# Main_Power.net
KiCad netlist of a schematic drawn in Altium Designer
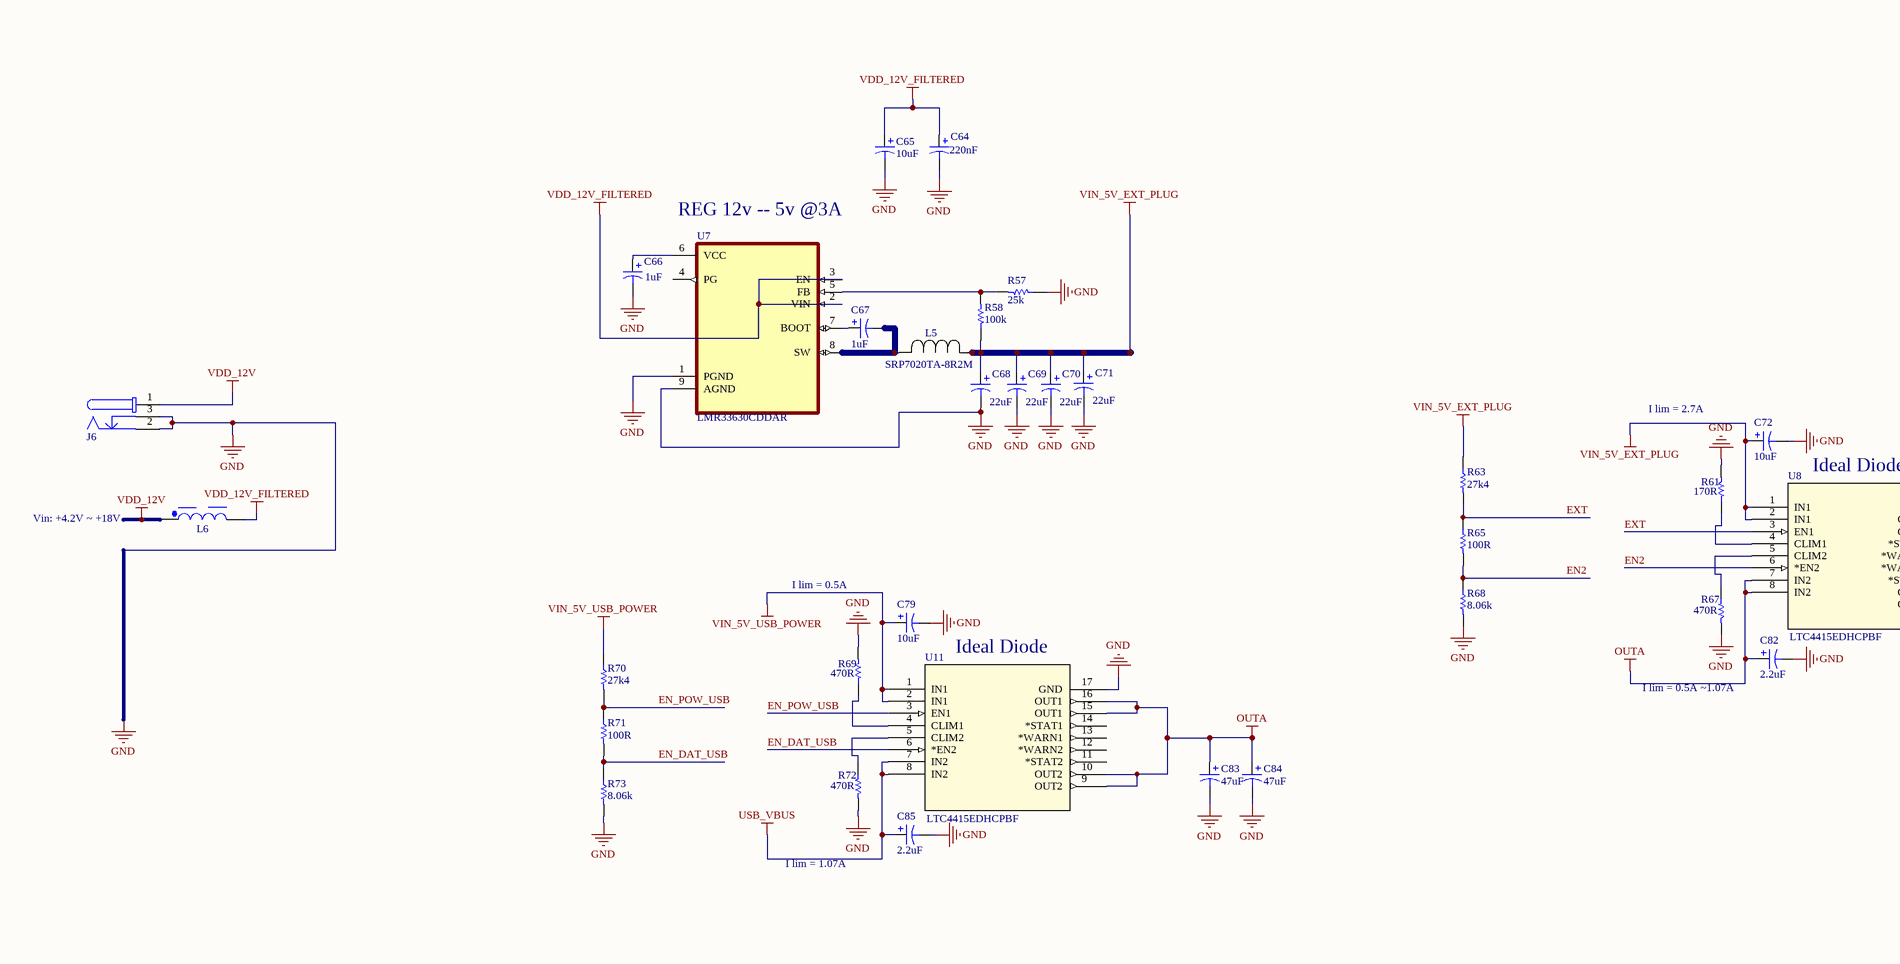
[diagram p0: Main_Power.SchDoc, top left]
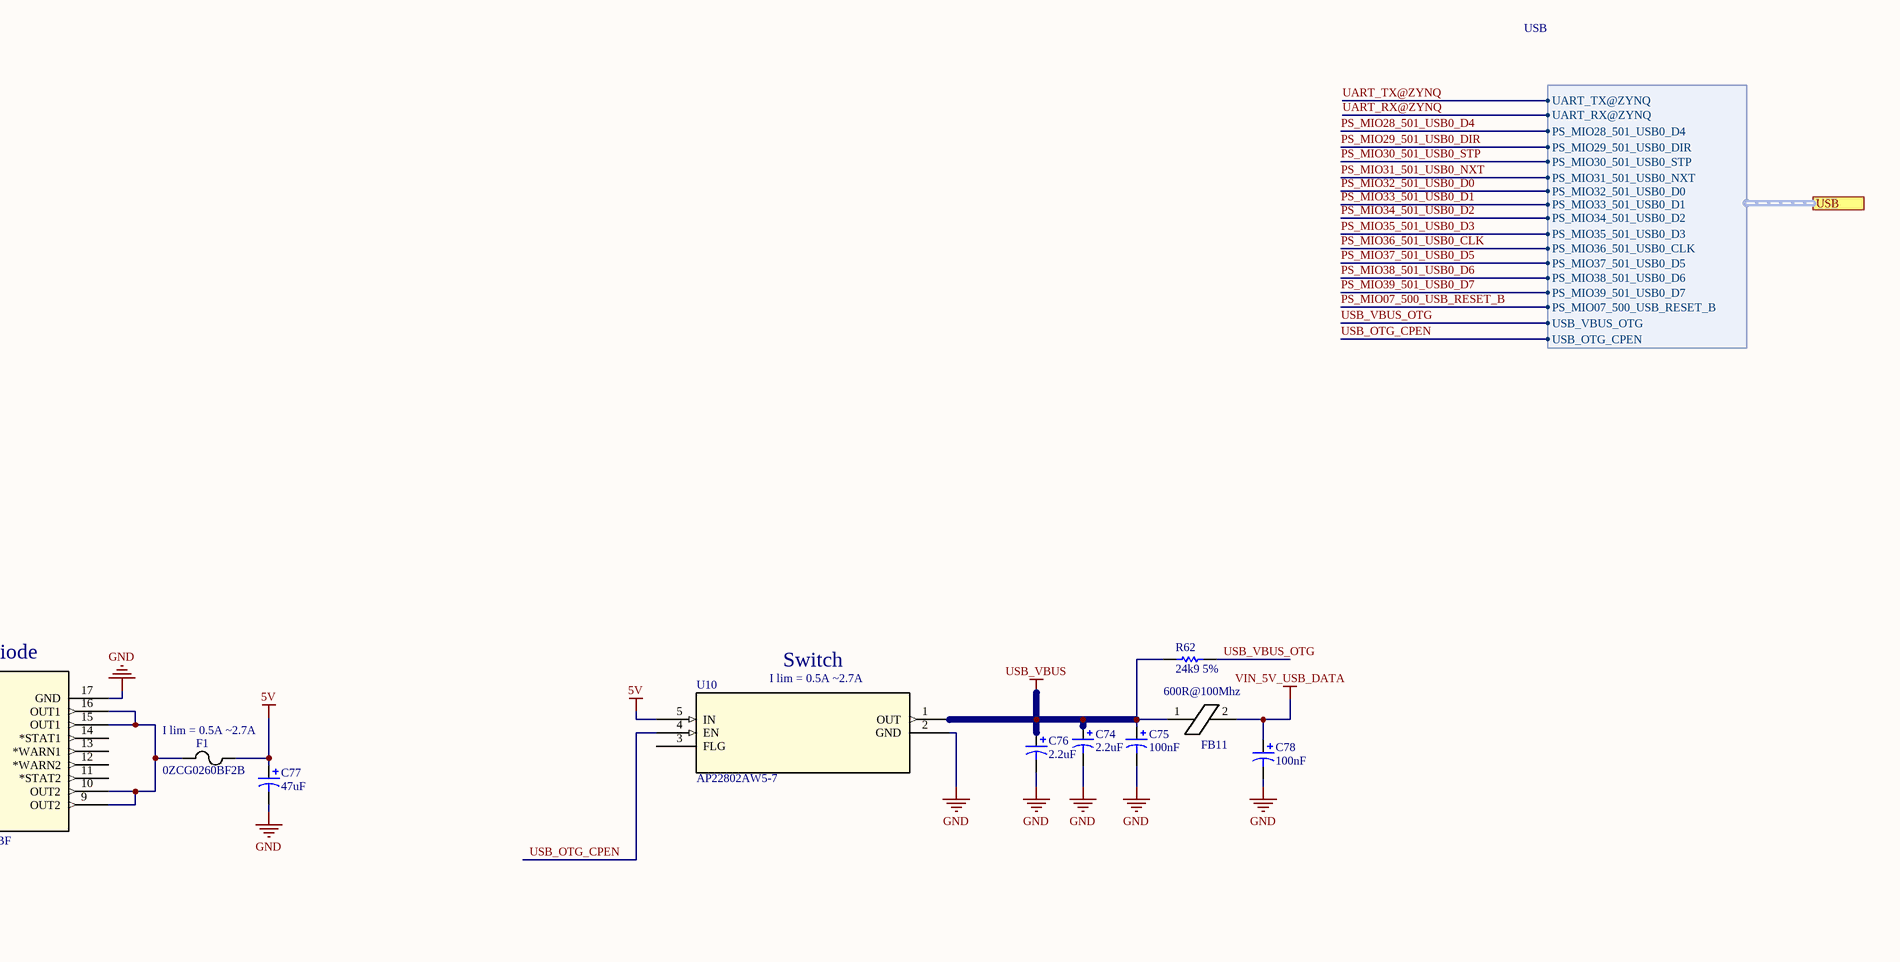
[diagram p1: Main_Power.SchDoc, top right]
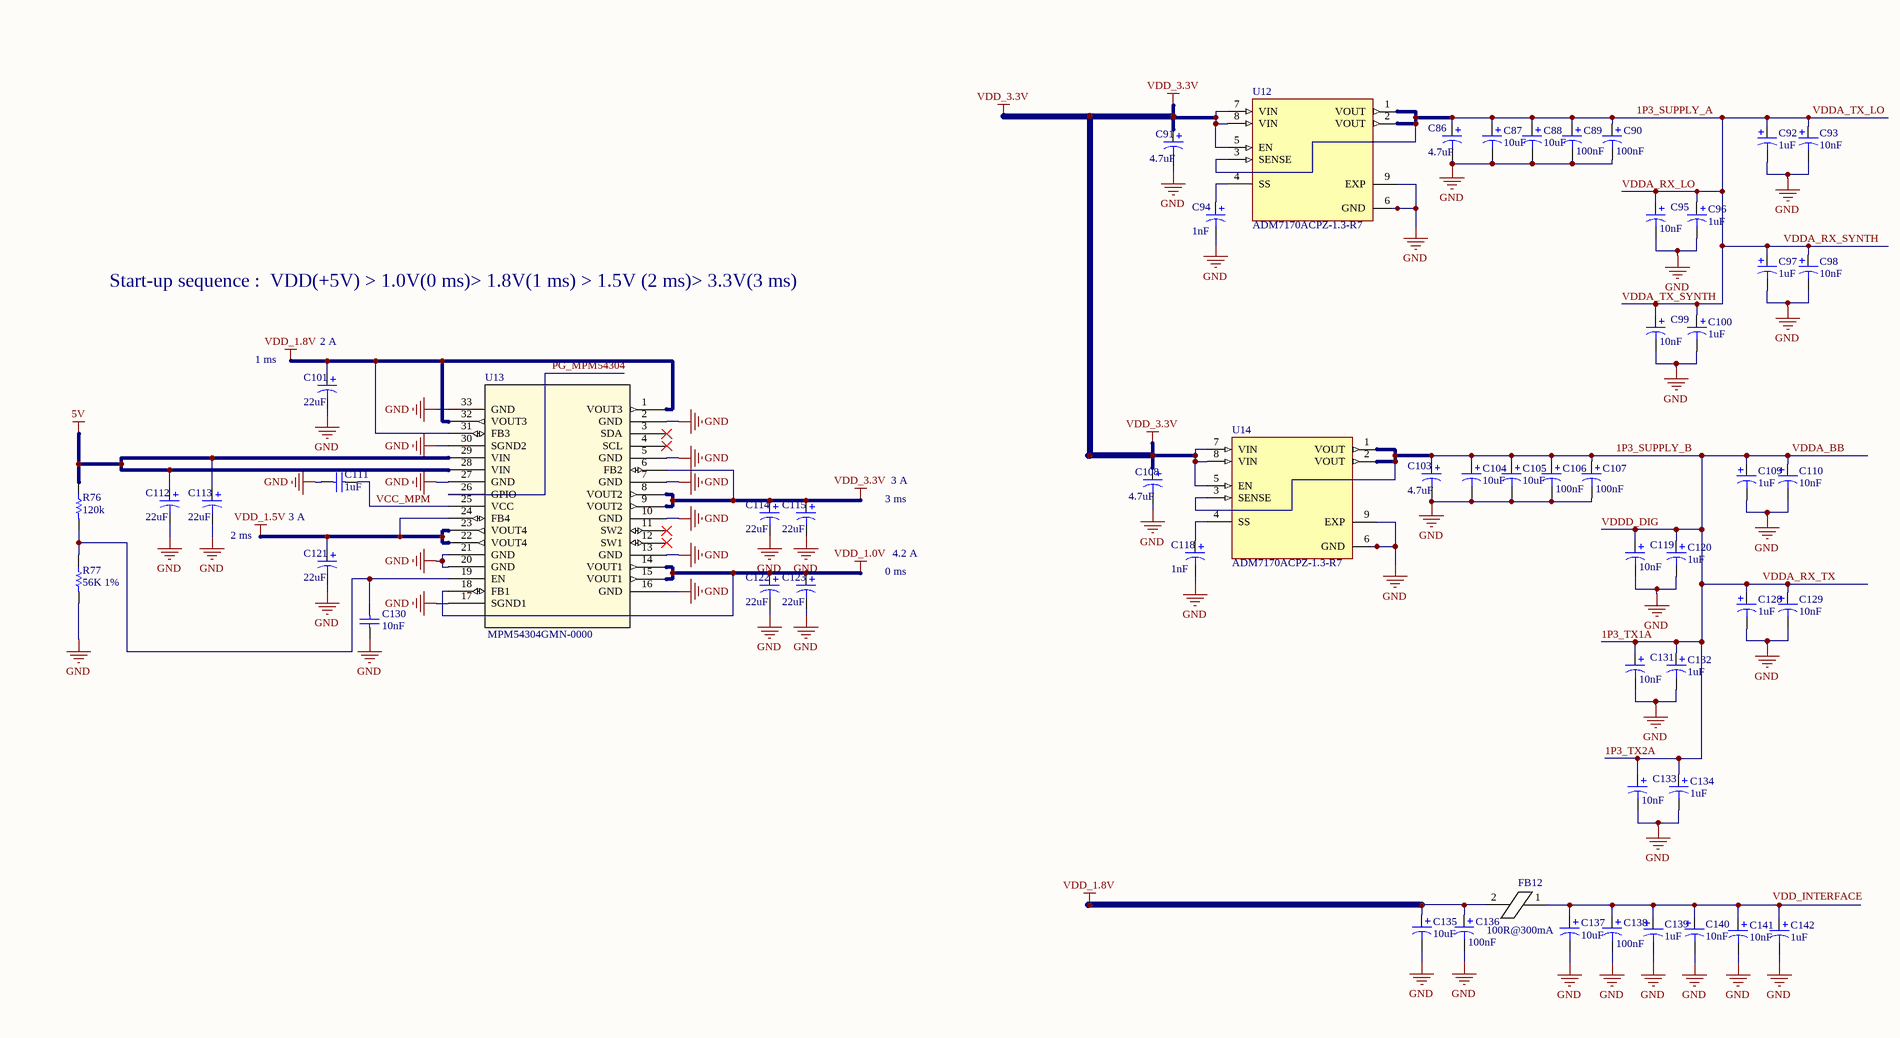
[diagram p2: Main_Power.SchDoc, bottom left]
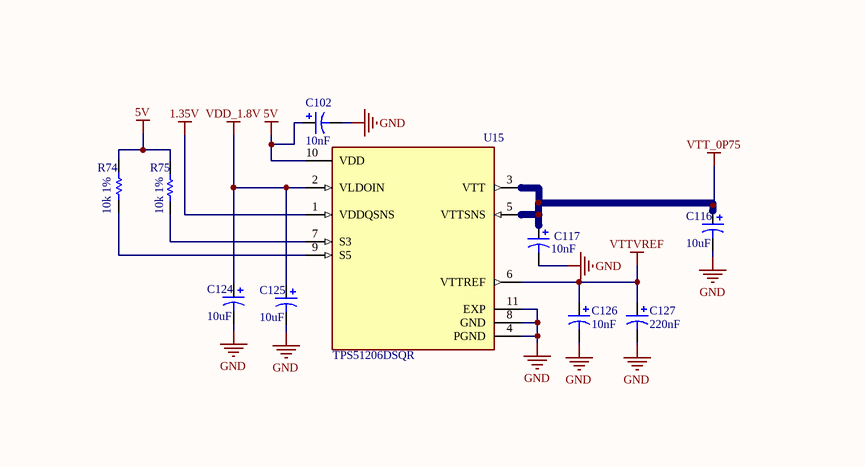
[diagram p3: Main_Power.SchDoc, bottom right]

(export (version "E")
  (design (tool "Eeschema 10.0.6"))
  (components
    (comp (ref "C64")
      (value "220nF")
      (footprint "C0805")
      (description "Polarized Capacitor (Surface Mount)")
      (fields (field (name "Comment") "Pol3") (field (name "PUBLISHER") "Altium Limited"))
      (libsource (lib "Miscellaneous Devices") (part "Cap Pol3"))
    )
    (comp (ref "C65")
      (value "10uF")
      (footprint "C0805")
      (description "Polarized Capacitor (Surface Mount)")
      (fields (field (name "Comment") "Cap Pol3") (field (name "PUBLISHER") "Altium Limited"))
      (libsource (lib "Miscellaneous Devices") (part "Cap Pol3"))
    )
    (comp (ref "C66")
      (value "1uF")
      (footprint "C0805")
      (description "Polarized Capacitor (Surface Mount)")
      (fields (field (name "Comment") "Pol3") (field (name "PUBLISHER") "Altium Limited"))
      (libsource (lib "Miscellaneous Devices") (part "Cap Pol3"))
    )
    (comp (ref "C67")
      (value "1uF")
      (footprint "C0805")
      (description "Polarized Capacitor (Surface Mount)")
      (fields (field (name "Comment") "Pol3") (field (name "PUBLISHER") "Altium Limited"))
      (libsource (lib "Miscellaneous Devices") (part "Cap Pol3"))
    )
    (comp (ref "C68")
      (value "22uF")
      (footprint "C0805")
      (description "Polarized Capacitor (Surface Mount)")
      (fields (field (name "Comment") "Pol3") (field (name "PUBLISHER") "Altium Limited"))
      (libsource (lib "Miscellaneous Devices") (part "Cap Pol3"))
    )
    (comp (ref "C69")
      (value "22uF")
      (footprint "C0805")
      (description "Polarized Capacitor (Surface Mount)")
      (fields (field (name "Comment") "Pol3") (field (name "PUBLISHER") "Altium Limited"))
      (libsource (lib "Miscellaneous Devices") (part "Cap Pol3"))
    )
    (comp (ref "C70")
      (value "22uF")
      (footprint "C0805")
      (description "Polarized Capacitor (Surface Mount)")
      (fields (field (name "Comment") "Pol3") (field (name "PUBLISHER") "Altium Limited"))
      (libsource (lib "Miscellaneous Devices") (part "Cap Pol3"))
    )
    (comp (ref "C71")
      (value "22uF")
      (footprint "C0805")
      (description "Polarized Capacitor (Surface Mount)")
      (fields (field (name "Comment") "Pol3") (field (name "PUBLISHER") "Altium Limited"))
      (libsource (lib "Miscellaneous Devices") (part "Cap Pol3"))
    )
    (comp (ref "C72")
      (value "10uF")
      (footprint "C0805")
      (description "Polarized Capacitor (Surface Mount)")
      (fields (field (name "Comment") "Cap Pol3") (field (name "PUBLISHER") "Altium Limited"))
      (libsource (lib "Miscellaneous Devices") (part "Cap Pol3"))
    )
    (comp (ref "C74")
      (value "2.2uF")
      (footprint "C0805")
      (description "Polarized Capacitor (Surface Mount)")
      (fields (field (name "Comment") "Cap Pol3") (field (name "PUBLISHER") "Altium Limited"))
      (libsource (lib "Miscellaneous Devices") (part "Cap Pol3"))
    )
    (comp (ref "C75")
      (value "100nF")
      (footprint "C0805")
      (description "Polarized Capacitor (Surface Mount)")
      (fields (field (name "Comment") "Cap Pol3") (field (name "PUBLISHER") "Altium Limited"))
      (libsource (lib "Miscellaneous Devices") (part "Cap Pol3"))
    )
    (comp (ref "C76")
      (value "2.2uF")
      (footprint "C0805")
      (description "Polarized Capacitor (Surface Mount)")
      (fields (field (name "Comment") "Cap Pol3") (field (name "PUBLISHER") "Altium Limited"))
      (libsource (lib "Miscellaneous Devices") (part "Cap Pol3"))
    )
    (comp (ref "C77")
      (value "47uF")
      (footprint "C0805")
      (description "Polarized Capacitor (Surface Mount)")
      (fields (field (name "Comment") "Cap Pol3") (field (name "PUBLISHER") "Altium Limited"))
      (libsource (lib "Miscellaneous Devices") (part "Cap Pol3"))
    )
    (comp (ref "C78")
      (value "100nF")
      (footprint "C0805")
      (description "Polarized Capacitor (Surface Mount)")
      (fields (field (name "Comment") "Cap Pol3") (field (name "PUBLISHER") "Altium Limited"))
      (libsource (lib "Miscellaneous Devices") (part "Cap Pol3"))
    )
    (comp (ref "C79")
      (value "10uF")
      (footprint "C0805")
      (description "Polarized Capacitor (Surface Mount)")
      (fields (field (name "Comment") "Cap Pol3") (field (name "PUBLISHER") "Altium Limited"))
      (libsource (lib "Miscellaneous Devices") (part "Cap Pol3"))
    )
    (comp (ref "C82")
      (value "2.2uF")
      (footprint "C0805")
      (description "Polarized Capacitor (Surface Mount)")
      (fields (field (name "Comment") "Cap Pol3") (field (name "PUBLISHER") "Altium Limited"))
      (libsource (lib "Miscellaneous Devices") (part "Cap Pol3"))
    )
    (comp (ref "C83")
      (value "47uF")
      (footprint "C0805")
      (description "Polarized Capacitor (Surface Mount)")
      (fields (field (name "Comment") "Cap Pol3") (field (name "PUBLISHER") "Altium Limited"))
      (libsource (lib "Miscellaneous Devices") (part "Cap Pol3"))
    )
    (comp (ref "C84")
      (value "47uF")
      (footprint "C0805")
      (description "Polarized Capacitor (Surface Mount)")
      (fields (field (name "Comment") "Cap Pol3") (field (name "PUBLISHER") "Altium Limited"))
      (libsource (lib "Miscellaneous Devices") (part "Cap Pol3"))
    )
    (comp (ref "C85")
      (value "2.2uF")
      (footprint "C0805")
      (description "Polarized Capacitor (Surface Mount)")
      (fields (field (name "Comment") "Cap Pol3") (field (name "PUBLISHER") "Altium Limited"))
      (libsource (lib "Miscellaneous Devices") (part "Cap Pol3"))
    )
    (comp (ref "C86")
      (value "4.7uF")
      (footprint "C0805")
      (description "Polarized Capacitor (Surface Mount)")
      (fields (field (name "Comment") "Pol3") (field (name "PUBLISHER") "Altium Limited"))
      (libsource (lib "Miscellaneous Devices") (part "Cap Pol3"))
    )
    (comp (ref "C87")
      (value "10uF")
      (footprint "C0805")
      (description "Polarized Capacitor (Surface Mount)")
      (fields (field (name "Comment") "Cap Pol3") (field (name "PUBLISHER") "Altium Limited"))
      (libsource (lib "Miscellaneous Devices") (part "Cap Pol3"))
    )
    (comp (ref "C88")
      (value "10uF")
      (footprint "C0805")
      (description "Polarized Capacitor (Surface Mount)")
      (fields (field (name "Comment") "Cap Pol3") (field (name "PUBLISHER") "Altium Limited"))
      (libsource (lib "Miscellaneous Devices") (part "Cap Pol3"))
    )
    (comp (ref "C89")
      (value "100nF")
      (footprint "C0805")
      (description "Polarized Capacitor (Surface Mount)")
      (fields (field (name "Comment") "Cap Pol3") (field (name "PUBLISHER") "Altium Limited"))
      (libsource (lib "Miscellaneous Devices") (part "Cap Pol3"))
    )
    (comp (ref "C90")
      (value "100nF")
      (footprint "C0805")
      (description "Polarized Capacitor (Surface Mount)")
      (fields (field (name "Comment") "Cap Pol3") (field (name "PUBLISHER") "Altium Limited"))
      (libsource (lib "Miscellaneous Devices") (part "Cap Pol3"))
    )
    (comp (ref "C91")
      (value "4.7uF")
      (footprint "C0805")
      (description "Polarized Capacitor (Surface Mount)")
      (fields (field (name "Comment") "Pol3") (field (name "PUBLISHER") "Altium Limited"))
      (libsource (lib "Miscellaneous Devices") (part "Cap Pol3"))
    )
    (comp (ref "C92")
      (value "1uF")
      (footprint "C0805")
      (description "Polarized Capacitor (Surface Mount)")
      (fields (field (name "Comment") "Cap Pol3") (field (name "PUBLISHER") "Altium Limited"))
      (libsource (lib "") (part "Cap Pol3_1"))
    )
    (comp (ref "C93")
      (value "10nF")
      (footprint "C0805")
      (description "Polarized Capacitor (Surface Mount)")
      (fields (field (name "Comment") "Cap Pol3") (field (name "PUBLISHER") "Altium Limited"))
      (libsource (lib "") (part "Cap Pol3_1"))
    )
    (comp (ref "C94")
      (value "1nF")
      (footprint "C0805")
      (description "Polarized Capacitor (Surface Mount)")
      (fields (field (name "Comment") "Pol3") (field (name "PUBLISHER") "Altium Limited"))
      (libsource (lib "Miscellaneous Devices") (part "Cap Pol3"))
    )
    (comp (ref "C95")
      (value "10nF")
      (footprint "C0805")
      (description "Polarized Capacitor (Surface Mount)")
      (fields (field (name "Comment") "Cap Pol3") (field (name "PUBLISHER") "Altium Limited"))
      (libsource (lib "Miscellaneous Devices") (part "Cap Pol3"))
    )
    (comp (ref "C96")
      (value "1uF")
      (footprint "C0805")
      (description "Polarized Capacitor (Surface Mount)")
      (fields (field (name "Comment") "Cap Pol3") (field (name "PUBLISHER") "Altium Limited"))
      (libsource (lib "Miscellaneous Devices") (part "Cap Pol3"))
    )
    (comp (ref "C97")
      (value "1uF")
      (footprint "C0805")
      (description "Polarized Capacitor (Surface Mount)")
      (fields (field (name "Comment") "Cap Pol3") (field (name "PUBLISHER") "Altium Limited"))
      (libsource (lib "") (part "Cap Pol3_1"))
    )
    (comp (ref "C98")
      (value "10nF")
      (footprint "C0805")
      (description "Polarized Capacitor (Surface Mount)")
      (fields (field (name "Comment") "Cap Pol3") (field (name "PUBLISHER") "Altium Limited"))
      (libsource (lib "") (part "Cap Pol3_1"))
    )
    (comp (ref "C99")
      (value "10nF")
      (footprint "C0805")
      (description "Polarized Capacitor (Surface Mount)")
      (fields (field (name "Comment") "Cap Pol3") (field (name "PUBLISHER") "Altium Limited"))
      (libsource (lib "Miscellaneous Devices") (part "Cap Pol3"))
    )
    (comp (ref "C100")
      (value "1uF")
      (footprint "C0805")
      (description "Polarized Capacitor (Surface Mount)")
      (fields (field (name "Comment") "Cap Pol3") (field (name "PUBLISHER") "Altium Limited"))
      (libsource (lib "Miscellaneous Devices") (part "Cap Pol3"))
    )
    (comp (ref "C101")
      (value "22uF")
      (footprint "C0805")
      (description "Polarized Capacitor (Surface Mount)")
      (fields (field (name "Comment") "Pol3") (field (name "PUBLISHER") "Altium Limited"))
      (libsource (lib "Miscellaneous Devices") (part "Cap Pol3"))
    )
    (comp (ref "C102")
      (value "10nF")
      (footprint "C0805")
      (description "Polarized Capacitor (Surface Mount)")
      (fields (field (name "Comment") "Cap Pol3") (field (name "PUBLISHER") "Altium Limited"))
      (libsource (lib "Miscellaneous Devices") (part "Cap Pol3"))
    )
    (comp (ref "C103")
      (value "4.7uF")
      (footprint "C0805")
      (description "Polarized Capacitor (Surface Mount)")
      (fields (field (name "Comment") "Pol3") (field (name "PUBLISHER") "Altium Limited"))
      (libsource (lib "Miscellaneous Devices") (part "Cap Pol3"))
    )
    (comp (ref "C104")
      (value "10uF")
      (footprint "C0805")
      (description "Polarized Capacitor (Surface Mount)")
      (fields (field (name "Comment") "Cap Pol3") (field (name "PUBLISHER") "Altium Limited"))
      (libsource (lib "Miscellaneous Devices") (part "Cap Pol3"))
    )
    (comp (ref "C105")
      (value "10uF")
      (footprint "C0805")
      (description "Polarized Capacitor (Surface Mount)")
      (fields (field (name "Comment") "Cap Pol3") (field (name "PUBLISHER") "Altium Limited"))
      (libsource (lib "Miscellaneous Devices") (part "Cap Pol3"))
    )
    (comp (ref "C106")
      (value "100nF")
      (footprint "C0805")
      (description "Polarized Capacitor (Surface Mount)")
      (fields (field (name "Comment") "Cap Pol3") (field (name "PUBLISHER") "Altium Limited"))
      (libsource (lib "Miscellaneous Devices") (part "Cap Pol3"))
    )
    (comp (ref "C107")
      (value "100nF")
      (footprint "C0805")
      (description "Polarized Capacitor (Surface Mount)")
      (fields (field (name "Comment") "Cap Pol3") (field (name "PUBLISHER") "Altium Limited"))
      (libsource (lib "Miscellaneous Devices") (part "Cap Pol3"))
    )
    (comp (ref "C108")
      (value "4.7uF")
      (footprint "C0805")
      (description "Polarized Capacitor (Surface Mount)")
      (fields (field (name "Comment") "Pol3") (field (name "PUBLISHER") "Altium Limited"))
      (libsource (lib "Miscellaneous Devices") (part "Cap Pol3"))
    )
    (comp (ref "C109")
      (value "1uF")
      (footprint "C0805")
      (description "Polarized Capacitor (Surface Mount)")
      (fields (field (name "Comment") "Cap Pol3") (field (name "PUBLISHER") "Altium Limited"))
      (libsource (lib "") (part "Cap Pol3_1"))
    )
    (comp (ref "C110")
      (value "10nF")
      (footprint "C0805")
      (description "Polarized Capacitor (Surface Mount)")
      (fields (field (name "Comment") "Cap Pol3") (field (name "PUBLISHER") "Altium Limited"))
      (libsource (lib "") (part "Cap Pol3_1"))
    )
    (comp (ref "C111")
      (value "1uF")
      (footprint "1608[0603]")
      (description "Capacitor (Semiconductor SIM Model)")
      (fields (field (name "PUBLISHER") "Altium Limited"))
      (libsource (lib "Miscellaneous Devices") (part "Cap Semi"))
    )
    (comp (ref "C112")
      (value "22uF")
      (footprint "C0805")
      (description "Polarized Capacitor (Surface Mount)")
      (fields (field (name "Comment") "Pol3") (field (name "PUBLISHER") "Altium Limited"))
      (libsource (lib "Miscellaneous Devices") (part "Cap Pol3"))
    )
    (comp (ref "C113")
      (value "22uF")
      (footprint "C0805")
      (description "Polarized Capacitor (Surface Mount)")
      (fields (field (name "Comment") "Pol3") (field (name "PUBLISHER") "Altium Limited"))
      (libsource (lib "Miscellaneous Devices") (part "Cap Pol3"))
    )
    (comp (ref "C114")
      (value "22uF")
      (footprint "C0805")
      (description "Polarized Capacitor (Surface Mount)")
      (fields (field (name "Comment") "Pol3") (field (name "PUBLISHER") "Altium Limited"))
      (libsource (lib "Miscellaneous Devices") (part "Cap Pol3"))
    )
    (comp (ref "C115")
      (value "22uF")
      (footprint "C0805")
      (description "Polarized Capacitor (Surface Mount)")
      (fields (field (name "Comment") "Pol3") (field (name "PUBLISHER") "Altium Limited"))
      (libsource (lib "Miscellaneous Devices") (part "Cap Pol3"))
    )
    (comp (ref "C116")
      (value "10uF")
      (footprint "C0805")
      (description "Polarized Capacitor (Surface Mount)")
      (fields (field (name "Comment") "Pol3") (field (name "PUBLISHER") "Altium Limited"))
      (libsource (lib "Miscellaneous Devices") (part "Cap Pol3"))
    )
    (comp (ref "C117")
      (value "10nF")
      (footprint "C0805")
      (description "Polarized Capacitor (Surface Mount)")
      (fields (field (name "Comment") "Cap Pol3") (field (name "PUBLISHER") "Altium Limited"))
      (libsource (lib "Miscellaneous Devices") (part "Cap Pol3"))
    )
    (comp (ref "C118")
      (value "1nF")
      (footprint "C0805")
      (description "Polarized Capacitor (Surface Mount)")
      (fields (field (name "Comment") "Pol3") (field (name "PUBLISHER") "Altium Limited"))
      (libsource (lib "Miscellaneous Devices") (part "Cap Pol3"))
    )
    (comp (ref "C119")
      (value "10nF")
      (footprint "C0805")
      (description "Polarized Capacitor (Surface Mount)")
      (fields (field (name "Comment") "Cap Pol3") (field (name "PUBLISHER") "Altium Limited"))
      (libsource (lib "Miscellaneous Devices") (part "Cap Pol3"))
    )
    (comp (ref "C120")
      (value "1uF")
      (footprint "C0805")
      (description "Polarized Capacitor (Surface Mount)")
      (fields (field (name "Comment") "Cap Pol3") (field (name "PUBLISHER") "Altium Limited"))
      (libsource (lib "Miscellaneous Devices") (part "Cap Pol3"))
    )
    (comp (ref "C121")
      (value "22uF")
      (footprint "C0805")
      (description "Polarized Capacitor (Surface Mount)")
      (fields (field (name "Comment") "Pol3") (field (name "PUBLISHER") "Altium Limited"))
      (libsource (lib "Miscellaneous Devices") (part "Cap Pol3"))
    )
    (comp (ref "C122")
      (value "22uF")
      (footprint "C0805")
      (description "Polarized Capacitor (Surface Mount)")
      (fields (field (name "Comment") "Pol3") (field (name "PUBLISHER") "Altium Limited"))
      (libsource (lib "Miscellaneous Devices") (part "Cap Pol3"))
    )
    (comp (ref "C123")
      (value "22uF")
      (footprint "C0805")
      (description "Polarized Capacitor (Surface Mount)")
      (fields (field (name "Comment") "Pol3") (field (name "PUBLISHER") "Altium Limited"))
      (libsource (lib "Miscellaneous Devices") (part "Cap Pol3"))
    )
    (comp (ref "C124")
      (value "10uF")
      (footprint "C0805")
      (description "Polarized Capacitor (Surface Mount)")
      (fields (field (name "Comment") "Pol3") (field (name "PUBLISHER") "Altium Limited"))
      (libsource (lib "Miscellaneous Devices") (part "Cap Pol3"))
    )
    (comp (ref "C125")
      (value "10uF")
      (footprint "C0805")
      (description "Polarized Capacitor (Surface Mount)")
      (fields (field (name "Comment") "Pol3") (field (name "PUBLISHER") "Altium Limited"))
      (libsource (lib "Miscellaneous Devices") (part "Cap Pol3"))
    )
    (comp (ref "C126")
      (value "10nF")
      (footprint "C0805")
      (description "Polarized Capacitor (Surface Mount)")
      (fields (field (name "Comment") "Cap Pol3") (field (name "PUBLISHER") "Altium Limited"))
      (libsource (lib "Miscellaneous Devices") (part "Cap Pol3"))
    )
    (comp (ref "C127")
      (value "220nF")
      (footprint "C0805")
      (description "Polarized Capacitor (Surface Mount)")
      (fields (field (name "Comment") "Cap Pol3") (field (name "PUBLISHER") "Altium Limited"))
      (libsource (lib "Miscellaneous Devices") (part "Cap Pol3"))
    )
    (comp (ref "C128")
      (value "1uF")
      (footprint "C0805")
      (description "Polarized Capacitor (Surface Mount)")
      (fields (field (name "Comment") "Cap Pol3") (field (name "PUBLISHER") "Altium Limited"))
      (libsource (lib "") (part "Cap Pol3_1"))
    )
    (comp (ref "C129")
      (value "10nF")
      (footprint "C0805")
      (description "Polarized Capacitor (Surface Mount)")
      (fields (field (name "Comment") "Cap Pol3") (field (name "PUBLISHER") "Altium Limited"))
      (libsource (lib "") (part "Cap Pol3_1"))
    )
    (comp (ref "C130")
      (value "10nF")
      (footprint "1608[0603]")
      (description "Capacitor (Semiconductor SIM Model)")
      (fields (field (name "PUBLISHER") "Altium Limited"))
      (libsource (lib "Miscellaneous Devices") (part "Cap Semi"))
    )
    (comp (ref "C131")
      (value "10nF")
      (footprint "C0805")
      (description "Polarized Capacitor (Surface Mount)")
      (fields (field (name "Comment") "Cap Pol3") (field (name "PUBLISHER") "Altium Limited"))
      (libsource (lib "Miscellaneous Devices") (part "Cap Pol3"))
    )
    (comp (ref "C132")
      (value "1uF")
      (footprint "C0805")
      (description "Polarized Capacitor (Surface Mount)")
      (fields (field (name "Comment") "Cap Pol3") (field (name "PUBLISHER") "Altium Limited"))
      (libsource (lib "Miscellaneous Devices") (part "Cap Pol3"))
    )
    (comp (ref "C133")
      (value "10nF")
      (footprint "C0805")
      (description "Polarized Capacitor (Surface Mount)")
      (fields (field (name "Comment") "Cap Pol3") (field (name "PUBLISHER") "Altium Limited"))
      (libsource (lib "Miscellaneous Devices") (part "Cap Pol3"))
    )
    (comp (ref "C134")
      (value "1uF")
      (footprint "C0805")
      (description "Polarized Capacitor (Surface Mount)")
      (fields (field (name "Comment") "Cap Pol3") (field (name "PUBLISHER") "Altium Limited"))
      (libsource (lib "Miscellaneous Devices") (part "Cap Pol3"))
    )
    (comp (ref "C135")
      (value "10uF")
      (footprint "C0805")
      (description "Polarized Capacitor (Surface Mount)")
      (fields (field (name "Comment") "Cap Pol3") (field (name "PUBLISHER") "Altium Limited"))
      (libsource (lib "Miscellaneous Devices") (part "Cap Pol3"))
    )
    (comp (ref "C136")
      (value "100nF")
      (footprint "C0805")
      (description "Polarized Capacitor (Surface Mount)")
      (fields (field (name "Comment") "Cap Pol3") (field (name "PUBLISHER") "Altium Limited"))
      (libsource (lib "Miscellaneous Devices") (part "Cap Pol3"))
    )
    (comp (ref "C137")
      (value "10uF")
      (footprint "C0805")
      (description "Polarized Capacitor (Surface Mount)")
      (fields (field (name "Comment") "Cap Pol3") (field (name "PUBLISHER") "Altium Limited"))
      (libsource (lib "Miscellaneous Devices") (part "Cap Pol3"))
    )
    (comp (ref "C138")
      (value "100nF")
      (footprint "C0805")
      (description "Polarized Capacitor (Surface Mount)")
      (fields (field (name "Comment") "Cap Pol3") (field (name "PUBLISHER") "Altium Limited"))
      (libsource (lib "Miscellaneous Devices") (part "Cap Pol3"))
    )
    (comp (ref "C139")
      (value "1uF")
      (footprint "C0805")
      (description "Polarized Capacitor (Surface Mount)")
      (fields (field (name "Comment") "Cap Pol3") (field (name "PUBLISHER") "Altium Limited"))
      (libsource (lib "") (part "Cap Pol3_1"))
    )
    (comp (ref "C140")
      (value "10nF")
      (footprint "C0805")
      (description "Polarized Capacitor (Surface Mount)")
      (fields (field (name "Comment") "Cap Pol3") (field (name "PUBLISHER") "Altium Limited"))
      (libsource (lib "") (part "Cap Pol3_1"))
    )
    (comp (ref "C141")
      (value "10nF")
      (footprint "C0805")
      (description "Polarized Capacitor (Surface Mount)")
      (fields (field (name "Comment") "Cap Pol3") (field (name "PUBLISHER") "Altium Limited"))
      (libsource (lib "Miscellaneous Devices") (part "Cap Pol3"))
    )
    (comp (ref "C142")
      (value "1uF")
      (footprint "C0805")
      (description "Polarized Capacitor (Surface Mount)")
      (fields (field (name "Comment") "Cap Pol3") (field (name "PUBLISHER") "Altium Limited"))
      (libsource (lib "Miscellaneous Devices") (part "Cap Pol3"))
    )
    (comp (ref "F1")
      (value "0ZCG0260BF2B")
      (footprint "0ZCG_BEL")
      (description "No Description Available")
      (libsource (lib "0ZCG0260BF2B") (part "0ZCG0260BF2B"))
    )
    (comp (ref "FB11")
      (value "FERRITA")
      (footprint "0805R")
      (libsource (lib "lib_protel_HC") (part "FERRITA"))
    )
    (comp (ref "FB12")
      (value "FERRITA")
      (footprint "0805R")
      (libsource (lib "lib_protel_HC") (part "FERRITA"))
    )
    (comp (ref "J6")
      (value "694108301002")
      (footprint "694108301002")
      (description "WR-DC DC Power Jack Connector, Male, Right Angled, 24V, 5A")
      (fields (field (name "MANUFACTURER") "Wurth Elektronik"))
      (libsource (lib "Altium_WR-DC (rev22a)") (part "694108301002"))
    )
    (comp (ref "L5")
      (value "SRP7020TA-8R2M")
      (footprint "IND_SRP7020TA-8R2M_BRN")
      (description "No Description Available")
      (libsource (lib "SRP7020TA-8R2M") (part "SRP7020TA-8R2M"))
    )
    (comp (ref "L6")
      (value "4.7uH, 2.9A")
      (footprint "WE-PD_7332R")
      (description "WE-PD SMT Power Inductor, size 7332R, 4.7uH, 2.9A, 39mOhm")
      (fields
        (field (name "MANUFACTURER PART NUMBER") "7447789004")
        (field (name "MANUFACTURER") "Wurth Elektronik")
      )
      (libsource (lib "Altium_WE-PD_rev22g") (part "7447789004"))
    )
    (comp (ref "R57")
      (value "25k")
      (footprint "0603")
      (description "Resistor")
      (fields
        (field (name "MANUFACTURER") "Generic Components")
        (field (name "Comment") "Res1")
        (field (name "PUBLISHER") "Altium Limited")
      )
      (libsource (lib "lib_protel_HC") (part "Res1_1"))
    )
    (comp (ref "R58")
      (value "100k")
      (footprint "0603")
      (description "Resistor")
      (fields
        (field (name "MANUFACTURER") "Generic Components")
        (field (name "Comment") "Res1")
        (field (name "PUBLISHER") "Altium Limited")
      )
      (libsource (lib "lib_protel_HC") (part "Res1_1"))
    )
    (comp (ref "R61")
      (value "170R")
      (footprint "0603")
      (description "Resistor")
      (fields
        (field (name "MANUFACTURER") "Generic Components")
        (field (name "Comment") "Res1")
        (field (name "PUBLISHER") "Altium Limited")
      )
      (libsource (lib "lib_protel_HC") (part "Res1_1"))
    )
    (comp (ref "R62")
      (value "24k9 5%")
      (footprint "0603")
      (description "Resistor")
      (fields
        (field (name "MANUFACTURER") "Generic Components")
        (field (name "Comment") "Res1")
        (field (name "PUBLISHER") "Altium Limited")
      )
      (libsource (lib "lib_protel_HC") (part "Res1_1"))
    )
    (comp (ref "R63")
      (value "27k4")
      (footprint "0603")
      (description "Resistor")
      (fields
        (field (name "MANUFACTURER") "Generic Components")
        (field (name "Comment") "Res1")
        (field (name "PUBLISHER") "Altium Limited")
      )
      (libsource (lib "lib_protel_HC") (part "Res1_1"))
    )
    (comp (ref "R65")
      (value "100R")
      (footprint "0603")
      (description "Resistor")
      (fields
        (field (name "MANUFACTURER") "Generic Components")
        (field (name "Comment") "Res1")
        (field (name "PUBLISHER") "Altium Limited")
      )
      (libsource (lib "lib_protel_HC") (part "Res1_1"))
    )
    (comp (ref "R67")
      (value "470R")
      (footprint "0603")
      (description "Resistor")
      (fields
        (field (name "MANUFACTURER") "Generic Components")
        (field (name "Comment") "Res1")
        (field (name "PUBLISHER") "Altium Limited")
      )
      (libsource (lib "lib_protel_HC") (part "Res1_1"))
    )
    (comp (ref "R68")
      (value "8.06k")
      (footprint "0603")
      (description "Resistor")
      (fields
        (field (name "MANUFACTURER") "Generic Components")
        (field (name "Comment") "Res1")
        (field (name "PUBLISHER") "Altium Limited")
      )
      (libsource (lib "lib_protel_HC") (part "Res1_1"))
    )
    (comp (ref "R69")
      (value "470R")
      (footprint "0603")
      (description "Resistor")
      (fields
        (field (name "MANUFACTURER") "Generic Components")
        (field (name "Comment") "Res1")
        (field (name "PUBLISHER") "Altium Limited")
      )
      (libsource (lib "lib_protel_HC") (part "Res1_1"))
    )
    (comp (ref "R70")
      (value "27k4")
      (footprint "0603")
      (description "Resistor")
      (fields
        (field (name "MANUFACTURER") "Generic Components")
        (field (name "Comment") "Res1")
        (field (name "PUBLISHER") "Altium Limited")
      )
      (libsource (lib "lib_protel_HC") (part "Res1_1"))
    )
    (comp (ref "R71")
      (value "100R")
      (footprint "0603")
      (description "Resistor")
      (fields
        (field (name "MANUFACTURER") "Generic Components")
        (field (name "Comment") "Res1")
        (field (name "PUBLISHER") "Altium Limited")
      )
      (libsource (lib "lib_protel_HC") (part "Res1_1"))
    )
    (comp (ref "R72")
      (value "470R")
      (footprint "0603")
      (description "Resistor")
      (fields
        (field (name "MANUFACTURER") "Generic Components")
        (field (name "Comment") "Res1")
        (field (name "PUBLISHER") "Altium Limited")
      )
      (libsource (lib "lib_protel_HC") (part "Res1_1"))
    )
    (comp (ref "R73")
      (value "8.06k")
      (footprint "0603")
      (description "Resistor")
      (fields
        (field (name "MANUFACTURER") "Generic Components")
        (field (name "Comment") "Res1")
        (field (name "PUBLISHER") "Altium Limited")
      )
      (libsource (lib "lib_protel_HC") (part "Res1_1"))
    )
    (comp (ref "R74")
      (value "10k 1%")
      (footprint "0603")
      (description "Resistor")
      (fields
        (field (name "MANUFACTURER") "Generic Components")
        (field (name "Comment") "Res1")
        (field (name "PUBLISHER") "Altium Limited")
      )
      (libsource (lib "lib_protel_HC") (part "Res1_1"))
    )
    (comp (ref "R75")
      (value "10k 1%")
      (footprint "0603")
      (description "Resistor")
      (fields
        (field (name "MANUFACTURER") "Generic Components")
        (field (name "Comment") "Res1")
        (field (name "PUBLISHER") "Altium Limited")
      )
      (libsource (lib "lib_protel_HC") (part "Res1_1"))
    )
    (comp (ref "R76")
      (value "120k")
      (footprint "0603")
      (description "Resistor")
      (fields
        (field (name "MANUFACTURER") "Generic Components")
        (field (name "Comment") "Res1")
        (field (name "PUBLISHER") "Altium Limited")
      )
      (libsource (lib "lib_protel_HC") (part "Res1_1"))
    )
    (comp (ref "R77")
      (value "56K 1%")
      (footprint "0603")
      (description "Resistor")
      (fields
        (field (name "MANUFACTURER") "Generic Components")
        (field (name "Comment") "Res1")
        (field (name "PUBLISHER") "Altium Limited")
      )
      (libsource (lib "lib_protel_HC") (part "Res1_1"))
    )
    (comp (ref "U7")
      (value "LMR33630CDDAR")
      (footprint "VREG_LM5017MR/NOPB")
      (fields (field (name "MF") "Texas Instruments"))
      (libsource (lib "LMR33630CDDAR") (part "LMR33630CDDAR"))
    )
    (comp (ref "U8")
      (value "LTC4415EDHCPBF")
      (footprint "05-08-1872_ADI")
      (description "No Description Available")
      (libsource (lib "LTC4415EDHCPBF") (part "LTC4415EDHCPBF"))
    )
    (comp (ref "U10")
      (value "AP22802AW5-7")
      (footprint "SOT25_DIO")
      (description "No Description Available")
      (libsource (lib "AP22802AW5-7") (part "AP22802AW5-7"))
    )
    (comp (ref "U11")
      (value "LTC4415EDHCPBF")
      (footprint "05-08-1872_ADI")
      (description "No Description Available")
      (libsource (lib "LTC4415EDHCPBF") (part "LTC4415EDHCPBF"))
    )
    (comp (ref "U12")
      (value "ADM7170ACPZ-1.3-R7")
      (footprint "SON50P300X300X80-9N")
      (description "6.5 V, 500 mA, Ultralow Noise, High PSRR, Fast Transient Response CMOS LDO")
      (fields (field (name "MF") "Analog Devices"))
      (libsource (lib "ADM7170ACPZ-1.3-R7") (part "ADM7170ACPZ-1.3-R7"))
    )
    (comp (ref "U13")
      (value "MPM54304GMN-0000")
      (footprint "LGA7x7x2_MNP")
      (description "No Description Available")
      (libsource (lib "MPM54304GMN-0000") (part "MPM54304GMN-0000"))
    )
    (comp (ref "U14")
      (value "ADM7170ACPZ-1.3-R7")
      (footprint "SON50P300X300X80-9N")
      (description "6.5 V, 500 mA, Ultralow Noise, High PSRR, Fast Transient Response CMOS LDO")
      (fields (field (name "MF") "Analog Devices"))
      (libsource (lib "ADM7170ACPZ-1.3-R7") (part "ADM7170ACPZ-1.3-R7"))
    )
    (comp (ref "U15")
      (value "TPS51206DSQR")
      (footprint "SON40P200X200X80-11N")
      (fields (field (name "MF") "Texas Instruments"))
      (libsource (lib "TPS51206DSQR") (part "TPS51206DSQR"))
    )
  )
  (nets
    (net (code "2") (name "/1P3_SUPPLY_A") (class "Default")
      (node (ref "C100") (pin "1") (pinfunction "1_1") (pintype "passive"))
      (node (ref "C86") (pin "1") (pinfunction "1_1") (pintype "passive"))
      (node (ref "C87") (pin "1") (pinfunction "1_1") (pintype "passive"))
      (node (ref "C88") (pin "1") (pinfunction "1_1") (pintype "passive"))
      (node (ref "C89") (pin "1") (pinfunction "1_1") (pintype "passive"))
      (node (ref "C90") (pin "1") (pinfunction "1_1") (pintype "passive"))
      (node (ref "C92") (pin "1") (pinfunction "1_1") (pintype "passive"))
      (node (ref "C93") (pin "1") (pinfunction "1_1") (pintype "passive"))
      (node (ref "C95") (pin "1") (pinfunction "1_1") (pintype "passive"))
      (node (ref "C96") (pin "1") (pinfunction "1_1") (pintype "passive"))
      (node (ref "C97") (pin "1") (pinfunction "1_1") (pintype "passive"))
      (node (ref "C98") (pin "1") (pinfunction "1_1") (pintype "passive"))
      (node (ref "C99") (pin "1") (pinfunction "1_1") (pintype "passive"))
      (node (ref "U12") (pin "1") (pinfunction "VOUT_1") (pintype "output"))
      (node (ref "U12") (pin "2") (pinfunction "VOUT_2") (pintype "output"))
      (node (ref "U12") (pin "3") (pinfunction "SENSE_3") (pintype "input"))
    )
    (net (code "3") (name "/1P3_SUPPLY_B") (class "Default")
      (node (ref "C103") (pin "1") (pinfunction "1_1") (pintype "passive"))
      (node (ref "C104") (pin "1") (pinfunction "1_1") (pintype "passive"))
      (node (ref "C105") (pin "1") (pinfunction "1_1") (pintype "passive"))
      (node (ref "C106") (pin "1") (pinfunction "1_1") (pintype "passive"))
      (node (ref "C107") (pin "1") (pinfunction "1_1") (pintype "passive"))
      (node (ref "C109") (pin "1") (pinfunction "1_1") (pintype "passive"))
      (node (ref "C110") (pin "1") (pinfunction "1_1") (pintype "passive"))
      (node (ref "C119") (pin "1") (pinfunction "1_1") (pintype "passive"))
      (node (ref "C120") (pin "1") (pinfunction "1_1") (pintype "passive"))
      (node (ref "C128") (pin "1") (pinfunction "1_1") (pintype "passive"))
      (node (ref "C129") (pin "1") (pinfunction "1_1") (pintype "passive"))
      (node (ref "C131") (pin "1") (pinfunction "1_1") (pintype "passive"))
      (node (ref "C132") (pin "1") (pinfunction "1_1") (pintype "passive"))
      (node (ref "C133") (pin "1") (pinfunction "1_1") (pintype "passive"))
      (node (ref "C134") (pin "1") (pinfunction "1_1") (pintype "passive"))
      (node (ref "U14") (pin "1") (pinfunction "VOUT_1") (pintype "output"))
      (node (ref "U14") (pin "2") (pinfunction "VOUT_2") (pintype "output"))
      (node (ref "U14") (pin "3") (pinfunction "SENSE_3") (pintype "input"))
    )
    (net (code "4") (name "/EN2") (class "Default")
      (node (ref "R65") (pin "2") (pinfunction "2_2") (pintype "passive"))
      (node (ref "R68") (pin "1") (pinfunction "1_1") (pintype "passive"))
      (node (ref "U8") (pin "6") (pinfunction "*EN2_6") (pintype "input"))
    )
    (net (code "5") (name "/EN_DAT_USB") (class "Default")
      (node (ref "R71") (pin "2") (pinfunction "2_2") (pintype "passive"))
      (node (ref "R73") (pin "1") (pinfunction "1_1") (pintype "passive"))
      (node (ref "U11") (pin "6") (pinfunction "*EN2_6") (pintype "input"))
    )
    (net (code "6") (name "/EN_POW_USB") (class "Default")
      (node (ref "R70") (pin "2") (pinfunction "2_2") (pintype "passive"))
      (node (ref "R71") (pin "1") (pinfunction "1_1") (pintype "passive"))
      (node (ref "U11") (pin "3") (pinfunction "EN1_3") (pintype "input"))
    )
    (net (code "7") (name "/EXT") (class "Default")
      (node (ref "R63") (pin "2") (pinfunction "2_2") (pintype "passive"))
      (node (ref "R65") (pin "1") (pinfunction "1_1") (pintype "passive"))
      (node (ref "U8") (pin "3") (pinfunction "EN1_3") (pintype "input"))
    )
    (net (code "8") (name "/PG_MPM54304") (class "Default")
      (node (ref "U13") (pin "26") (pinfunction "GPIO_26") (pintype "passive"))
    )
    (net (code "24") (name "/USB_OTG_CPEN") (class "Default")
      (node (ref "U10") (pin "4") (pinfunction "EN_4") (pintype "input"))
    )
    (net (code "25") (name "/USB_VBUS_OTG") (class "Default")
      (node (ref "R62") (pin "1") (pinfunction "1_1") (pintype "passive"))
    )
    (net (code "26") (name "/VCC_MPM") (class "Default")
      (node (ref "C111") (pin "1") (pinfunction "1_1") (pintype "passive"))
      (node (ref "U13") (pin "25") (pinfunction "VCC_25") (pintype "power_in"))
    )
    (net (code "29") (name "1.35V") (class "Default")
      (node (ref "U15") (pin "1") (pinfunction "VDDQSNS_1") (pintype "input"))
    )
    (net (code "30") (name "5V") (class "Default")
      (node (ref "C102") (pin "1") (pinfunction "1_1") (pintype "passive"))
      (node (ref "C112") (pin "1") (pinfunction "1_1") (pintype "passive"))
      (node (ref "C113") (pin "1") (pinfunction "1_1") (pintype "passive"))
      (node (ref "C77") (pin "1") (pinfunction "1_1") (pintype "passive"))
      (node (ref "F1") (pin "2") (pinfunction "2_2") (pintype "passive"))
      (node (ref "R74") (pin "2") (pinfunction "2_2") (pintype "passive"))
      (node (ref "R75") (pin "2") (pinfunction "2_2") (pintype "passive"))
      (node (ref "R76") (pin "1") (pinfunction "1_1") (pintype "passive"))
      (node (ref "U10") (pin "5") (pinfunction "IN_5") (pintype "input"))
      (node (ref "U13") (pin "28") (pinfunction "VIN_28") (pintype "passive"))
      (node (ref "U13") (pin "29") (pinfunction "VIN_29") (pintype "passive"))
      (node (ref "U15") (pin "10") (pinfunction "VDD_10") (pintype "power_in"))
    )
    (net (code "31") (name "GND") (class "Default")
      (node (ref "C100") (pin "2") (pinfunction "2_2") (pintype "passive"))
      (node (ref "C101") (pin "2") (pinfunction "2_2") (pintype "passive"))
      (node (ref "C102") (pin "2") (pinfunction "2_2") (pintype "passive"))
      (node (ref "C103") (pin "2") (pinfunction "2_2") (pintype "passive"))
      (node (ref "C104") (pin "2") (pinfunction "2_2") (pintype "passive"))
      (node (ref "C105") (pin "2") (pinfunction "2_2") (pintype "passive"))
      (node (ref "C106") (pin "2") (pinfunction "2_2") (pintype "passive"))
      (node (ref "C107") (pin "2") (pinfunction "2_2") (pintype "passive"))
      (node (ref "C108") (pin "2") (pinfunction "2_2") (pintype "passive"))
      (node (ref "C109") (pin "2") (pinfunction "2_2") (pintype "passive"))
      (node (ref "C110") (pin "2") (pinfunction "2_2") (pintype "passive"))
      (node (ref "C111") (pin "2") (pinfunction "2_2") (pintype "passive"))
      (node (ref "C112") (pin "2") (pinfunction "2_2") (pintype "passive"))
      (node (ref "C113") (pin "2") (pinfunction "2_2") (pintype "passive"))
      (node (ref "C114") (pin "2") (pinfunction "2_2") (pintype "passive"))
      (node (ref "C115") (pin "2") (pinfunction "2_2") (pintype "passive"))
      (node (ref "C116") (pin "2") (pinfunction "2_2") (pintype "passive"))
      (node (ref "C117") (pin "2") (pinfunction "2_2") (pintype "passive"))
      (node (ref "C118") (pin "2") (pinfunction "2_2") (pintype "passive"))
      (node (ref "C119") (pin "2") (pinfunction "2_2") (pintype "passive"))
      (node (ref "C120") (pin "2") (pinfunction "2_2") (pintype "passive"))
      (node (ref "C121") (pin "2") (pinfunction "2_2") (pintype "passive"))
      (node (ref "C122") (pin "2") (pinfunction "2_2") (pintype "passive"))
      (node (ref "C123") (pin "2") (pinfunction "2_2") (pintype "passive"))
      (node (ref "C124") (pin "2") (pinfunction "2_2") (pintype "passive"))
      (node (ref "C125") (pin "2") (pinfunction "2_2") (pintype "passive"))
      (node (ref "C126") (pin "2") (pinfunction "2_2") (pintype "passive"))
      (node (ref "C127") (pin "2") (pinfunction "2_2") (pintype "passive"))
      (node (ref "C128") (pin "2") (pinfunction "2_2") (pintype "passive"))
      (node (ref "C129") (pin "2") (pinfunction "2_2") (pintype "passive"))
      (node (ref "C130") (pin "2") (pinfunction "2_2") (pintype "passive"))
      (node (ref "C131") (pin "2") (pinfunction "2_2") (pintype "passive"))
      (node (ref "C132") (pin "2") (pinfunction "2_2") (pintype "passive"))
      (node (ref "C133") (pin "2") (pinfunction "2_2") (pintype "passive"))
      (node (ref "C134") (pin "2") (pinfunction "2_2") (pintype "passive"))
      (node (ref "C135") (pin "2") (pinfunction "2_2") (pintype "passive"))
      (node (ref "C136") (pin "2") (pinfunction "2_2") (pintype "passive"))
      (node (ref "C137") (pin "2") (pinfunction "2_2") (pintype "passive"))
      (node (ref "C138") (pin "2") (pinfunction "2_2") (pintype "passive"))
      (node (ref "C139") (pin "2") (pinfunction "2_2") (pintype "passive"))
      (node (ref "C140") (pin "2") (pinfunction "2_2") (pintype "passive"))
      (node (ref "C141") (pin "2") (pinfunction "2_2") (pintype "passive"))
      (node (ref "C142") (pin "2") (pinfunction "2_2") (pintype "passive"))
      (node (ref "C64") (pin "2") (pinfunction "2_2") (pintype "passive"))
      (node (ref "C65") (pin "2") (pinfunction "2_2") (pintype "passive"))
      (node (ref "C66") (pin "2") (pinfunction "2_2") (pintype "passive"))
      (node (ref "C68") (pin "2") (pinfunction "2_2") (pintype "passive"))
      (node (ref "C69") (pin "2") (pinfunction "2_2") (pintype "passive"))
      (node (ref "C70") (pin "2") (pinfunction "2_2") (pintype "passive"))
      (node (ref "C71") (pin "2") (pinfunction "2_2") (pintype "passive"))
      (node (ref "C72") (pin "2") (pinfunction "2_2") (pintype "passive"))
      (node (ref "C74") (pin "2") (pinfunction "2_2") (pintype "passive"))
      (node (ref "C75") (pin "2") (pinfunction "2_2") (pintype "passive"))
      (node (ref "C76") (pin "2") (pinfunction "2_2") (pintype "passive"))
      (node (ref "C77") (pin "2") (pinfunction "2_2") (pintype "passive"))
      (node (ref "C78") (pin "2") (pinfunction "2_2") (pintype "passive"))
      (node (ref "C79") (pin "2") (pinfunction "2_2") (pintype "passive"))
      (node (ref "C82") (pin "2") (pinfunction "2_2") (pintype "passive"))
      (node (ref "C83") (pin "2") (pinfunction "2_2") (pintype "passive"))
      (node (ref "C84") (pin "2") (pinfunction "2_2") (pintype "passive"))
      (node (ref "C85") (pin "2") (pinfunction "2_2") (pintype "passive"))
      (node (ref "C86") (pin "2") (pinfunction "2_2") (pintype "passive"))
      (node (ref "C87") (pin "2") (pinfunction "2_2") (pintype "passive"))
      (node (ref "C88") (pin "2") (pinfunction "2_2") (pintype "passive"))
      (node (ref "C89") (pin "2") (pinfunction "2_2") (pintype "passive"))
      (node (ref "C90") (pin "2") (pinfunction "2_2") (pintype "passive"))
      (node (ref "C91") (pin "2") (pinfunction "2_2") (pintype "passive"))
      (node (ref "C92") (pin "2") (pinfunction "2_2") (pintype "passive"))
      (node (ref "C93") (pin "2") (pinfunction "2_2") (pintype "passive"))
      (node (ref "C94") (pin "2") (pinfunction "2_2") (pintype "passive"))
      (node (ref "C95") (pin "2") (pinfunction "2_2") (pintype "passive"))
      (node (ref "C96") (pin "2") (pinfunction "2_2") (pintype "passive"))
      (node (ref "C97") (pin "2") (pinfunction "2_2") (pintype "passive"))
      (node (ref "C98") (pin "2") (pinfunction "2_2") (pintype "passive"))
      (node (ref "C99") (pin "2") (pinfunction "2_2") (pintype "passive"))
      (node (ref "J6") (pin "2") (pinfunction "2_2") (pintype "passive"))
      (node (ref "J6") (pin "3") (pinfunction "3_3") (pintype "passive"))
      (node (ref "R57") (pin "1") (pinfunction "1_1") (pintype "passive"))
      (node (ref "R61") (pin "2") (pinfunction "2_2") (pintype "passive"))
      (node (ref "R67") (pin "2") (pinfunction "2_2") (pintype "passive"))
      (node (ref "R68") (pin "2") (pinfunction "2_2") (pintype "passive"))
      (node (ref "R69") (pin "2") (pinfunction "2_2") (pintype "passive"))
      (node (ref "R72") (pin "2") (pinfunction "2_2") (pintype "passive"))
      (node (ref "R73") (pin "2") (pinfunction "2_2") (pintype "passive"))
      (node (ref "R77") (pin "2") (pinfunction "2_2") (pintype "passive"))
      (node (ref "U10") (pin "2") (pinfunction "GND_2") (pintype "power_in"))
      (node (ref "U11") (pin "17") (pinfunction "GND_17") (pintype "power_in"))
      (node (ref "U12") (pin "6") (pinfunction "GND_6") (pintype "power_in"))
      (node (ref "U12") (pin "9") (pinfunction "EXP_9") (pintype "power_in"))
      (node (ref "U13") (pin "10") (pinfunction "GND_10") (pintype "power_in"))
      (node (ref "U13") (pin "13") (pinfunction "GND_13") (pintype "power_in"))
      (node (ref "U13") (pin "16") (pinfunction "GND_16") (pintype "power_in"))
      (node (ref "U13") (pin "17") (pinfunction "SGND1_17") (pintype "power_in"))
      (node (ref "U13") (pin "2") (pinfunction "GND_2") (pintype "power_in"))
      (node (ref "U13") (pin "20") (pinfunction "GND_20") (pintype "power_in"))
      (node (ref "U13") (pin "21") (pinfunction "GND_21") (pintype "power_in"))
      (node (ref "U13") (pin "27") (pinfunction "GND_27") (pintype "power_in"))
      (node (ref "U13") (pin "30") (pinfunction "SGND2_30") (pintype "power_in"))
      (node (ref "U13") (pin "33") (pinfunction "GND_33") (pintype "power_in"))
      (node (ref "U13") (pin "5") (pinfunction "GND_5") (pintype "power_in"))
      (node (ref "U13") (pin "7") (pinfunction "GND_7") (pintype "power_in"))
      (node (ref "U14") (pin "6") (pinfunction "GND_6") (pintype "power_in"))
      (node (ref "U14") (pin "9") (pinfunction "EXP_9") (pintype "power_in"))
      (node (ref "U15") (pin "11") (pinfunction "EXP_11") (pintype "passive"))
      (node (ref "U15") (pin "4") (pinfunction "PGND_4") (pintype "power_in"))
      (node (ref "U15") (pin "8") (pinfunction "GND_8") (pintype "power_in"))
      (node (ref "U7") (pin "1") (pinfunction "PGND_1") (pintype "power_in"))
      (node (ref "U7") (pin "9") (pinfunction "AGND_9") (pintype "power_in"))
      (node (ref "U8") (pin "17") (pinfunction "GND_17") (pintype "power_in"))
    )
    (net (code "32") (name "Net-(C137-Pad1)") (class "Default")
      (node (ref "C137") (pin "1") (pinfunction "1_1") (pintype "passive"))
      (node (ref "C138") (pin "1") (pinfunction "1_1") (pintype "passive"))
      (node (ref "C139") (pin "1") (pinfunction "1_1") (pintype "passive"))
      (node (ref "C140") (pin "1") (pinfunction "1_1") (pintype "passive"))
      (node (ref "C141") (pin "1") (pinfunction "1_1") (pintype "passive"))
      (node (ref "C142") (pin "1") (pinfunction "1_1") (pintype "passive"))
      (node (ref "FB12") (pin "1") (pintype "passive"))
    )
    (net (code "33") (name "Net-(F1-Pad1)") (class "Default")
      (node (ref "F1") (pin "1") (pinfunction "1_1") (pintype "passive"))
      (node (ref "U8") (pin "10") (pinfunction "OUT2_10") (pintype "output"))
      (node (ref "U8") (pin "15") (pinfunction "OUT1_15") (pintype "output"))
      (node (ref "U8") (pin "16") (pinfunction "OUT1_16") (pintype "output"))
      (node (ref "U8") (pin "9") (pinfunction "OUT2_9") (pintype "output"))
    )
    (net (code "34") (name "Net-(U7-BOOT)") (class "Default")
      (node (ref "C67") (pin "1") (pinfunction "1_1") (pintype "passive"))
      (node (ref "U7") (pin "7") (pinfunction "BOOT_7") (pintype "bidirectional"))
    )
    (net (code "35") (name "Net-(U7-FB)") (class "Default")
      (node (ref "R57") (pin "2") (pinfunction "2_2") (pintype "passive"))
      (node (ref "R58") (pin "2") (pinfunction "2_2") (pintype "passive"))
      (node (ref "U7") (pin "5") (pinfunction "FB_5") (pintype "input"))
    )
    (net (code "36") (name "Net-(U7-SW)") (class "Default")
      (node (ref "C67") (pin "2") (pinfunction "2_2") (pintype "passive"))
      (node (ref "L5") (pin "2") (pinfunction "2_2") (pintype "passive"))
      (node (ref "U7") (pin "8") (pinfunction "SW_8") (pintype "bidirectional"))
    )
    (net (code "37") (name "Net-(U7-VCC)") (class "Default")
      (node (ref "C66") (pin "1") (pinfunction "1_1") (pintype "passive"))
      (node (ref "U7") (pin "6") (pinfunction "VCC_6") (pintype "power_in"))
    )
    (net (code "38") (name "Net-(U8-CLIM1)") (class "Default")
      (node (ref "R61") (pin "1") (pinfunction "1_1") (pintype "passive"))
      (node (ref "U8") (pin "4") (pinfunction "CLIM1_4") (pintype "passive"))
    )
    (net (code "39") (name "Net-(U8-CLIM2)") (class "Default")
      (node (ref "R67") (pin "1") (pinfunction "1_1") (pintype "passive"))
      (node (ref "U8") (pin "5") (pinfunction "CLIM2_5") (pintype "passive"))
    )
    (net (code "40") (name "Net-(U11-CLIM1)") (class "Default")
      (node (ref "R69") (pin "1") (pinfunction "1_1") (pintype "passive"))
      (node (ref "U11") (pin "4") (pinfunction "CLIM1_4") (pintype "passive"))
    )
    (net (code "41") (name "Net-(U11-CLIM2)") (class "Default")
      (node (ref "R72") (pin "1") (pinfunction "1_1") (pintype "passive"))
      (node (ref "U11") (pin "5") (pinfunction "CLIM2_5") (pintype "passive"))
    )
    (net (code "42") (name "Net-(U12-SS)") (class "Default")
      (node (ref "C94") (pin "1") (pinfunction "1_1") (pintype "passive"))
      (node (ref "U12") (pin "4") (pinfunction "SS_4") (pintype "passive"))
    )
    (net (code "43") (name "Net-(U13-EN)") (class "Default")
      (node (ref "C130") (pin "1") (pinfunction "1_1") (pintype "passive"))
      (node (ref "R76") (pin "2") (pinfunction "2_2") (pintype "passive"))
      (node (ref "R77") (pin "1") (pinfunction "1_1") (pintype "passive"))
      (node (ref "U13") (pin "19") (pinfunction "EN_19") (pintype "passive"))
    )
    (net (code "44") (name "Net-(U14-SS)") (class "Default")
      (node (ref "C118") (pin "1") (pinfunction "1_1") (pintype "passive"))
      (node (ref "U14") (pin "4") (pinfunction "SS_4") (pintype "passive"))
    )
    (net (code "45") (name "Net-(U15-S3)") (class "Default")
      (node (ref "R75") (pin "1") (pinfunction "1_1") (pintype "passive"))
      (node (ref "U15") (pin "7") (pinfunction "S3_7") (pintype "input"))
    )
    (net (code "46") (name "Net-(U15-S5)") (class "Default")
      (node (ref "R74") (pin "1") (pinfunction "1_1") (pintype "passive"))
      (node (ref "U15") (pin "9") (pinfunction "S5_9") (pintype "input"))
    )
    (net (code "47") (name "OUTA") (class "Default")
      (node (ref "C82") (pin "1") (pinfunction "1_1") (pintype "passive"))
      (node (ref "C83") (pin "1") (pinfunction "1_1") (pintype "passive"))
      (node (ref "C84") (pin "1") (pinfunction "1_1") (pintype "passive"))
      (node (ref "U11") (pin "10") (pinfunction "OUT2_10") (pintype "output"))
      (node (ref "U11") (pin "15") (pinfunction "OUT1_15") (pintype "output"))
      (node (ref "U11") (pin "16") (pinfunction "OUT1_16") (pintype "output"))
      (node (ref "U11") (pin "9") (pinfunction "OUT2_9") (pintype "output"))
      (node (ref "U8") (pin "7") (pinfunction "IN2_7") (pintype "power_in"))
      (node (ref "U8") (pin "8") (pinfunction "IN2_8") (pintype "power_in"))
    )
    (net (code "48") (name "USB_VBUS") (class "Default")
      (node (ref "C74") (pin "1") (pinfunction "1_1") (pintype "passive"))
      (node (ref "C75") (pin "1") (pinfunction "1_1") (pintype "passive"))
      (node (ref "C76") (pin "1") (pinfunction "1_1") (pintype "passive"))
      (node (ref "C85") (pin "1") (pinfunction "1_1") (pintype "passive"))
      (node (ref "FB11") (pin "1") (pintype "passive"))
      (node (ref "R62") (pin "2") (pinfunction "2_2") (pintype "passive"))
      (node (ref "U10") (pin "1") (pinfunction "OUT_1") (pintype "output"))
      (node (ref "U11") (pin "7") (pinfunction "IN2_7") (pintype "power_in"))
      (node (ref "U11") (pin "8") (pinfunction "IN2_8") (pintype "power_in"))
    )
    (net (code "49") (name "VDD_1.0V") (class "Default")
      (node (ref "C122") (pin "1") (pinfunction "1_1") (pintype "passive"))
      (node (ref "C123") (pin "1") (pinfunction "1_1") (pintype "passive"))
      (node (ref "U13") (pin "14") (pinfunction "VOUT1_14") (pintype "output"))
      (node (ref "U13") (pin "15") (pinfunction "VOUT1_15") (pintype "output"))
      (node (ref "U13") (pin "18") (pinfunction "FB1_18") (pintype "bidirectional"))
    )
    (net (code "50") (name "VDD_1.5V") (class "Default")
      (node (ref "C121") (pin "1") (pinfunction "1_1") (pintype "passive"))
      (node (ref "U13") (pin "22") (pinfunction "VOUT4_22") (pintype "output"))
      (node (ref "U13") (pin "23") (pinfunction "VOUT4_23") (pintype "output"))
      (node (ref "U13") (pin "24") (pinfunction "FB4_24") (pintype "bidirectional"))
    )
    (net (code "51") (name "VDD_1.8V") (class "Default")
      (node (ref "C101") (pin "1") (pinfunction "1_1") (pintype "passive"))
      (node (ref "C124") (pin "1") (pinfunction "1_1") (pintype "passive"))
      (node (ref "C125") (pin "1") (pinfunction "1_1") (pintype "passive"))
      (node (ref "C135") (pin "1") (pinfunction "1_1") (pintype "passive"))
      (node (ref "C136") (pin "1") (pinfunction "1_1") (pintype "passive"))
      (node (ref "FB12") (pin "2") (pintype "passive"))
      (node (ref "U13") (pin "1") (pinfunction "VOUT3_1") (pintype "output"))
      (node (ref "U13") (pin "31") (pinfunction "FB3_31") (pintype "bidirectional"))
      (node (ref "U13") (pin "32") (pinfunction "VOUT3_32") (pintype "output"))
      (node (ref "U15") (pin "2") (pinfunction "VLDOIN_2") (pintype "input"))
    )
    (net (code "52") (name "VDD_3.3V") (class "Default")
      (node (ref "C108") (pin "1") (pinfunction "1_1") (pintype "passive"))
      (node (ref "C114") (pin "1") (pinfunction "1_1") (pintype "passive"))
      (node (ref "C115") (pin "1") (pinfunction "1_1") (pintype "passive"))
      (node (ref "C91") (pin "1") (pinfunction "1_1") (pintype "passive"))
      (node (ref "U12") (pin "5") (pinfunction "EN_5") (pintype "input"))
      (node (ref "U12") (pin "7") (pinfunction "VIN_7") (pintype "input"))
      (node (ref "U12") (pin "8") (pinfunction "VIN_8") (pintype "input"))
      (node (ref "U13") (pin "6") (pinfunction "FB2_6") (pintype "bidirectional"))
      (node (ref "U13") (pin "8") (pinfunction "VOUT2_8") (pintype "output"))
      (node (ref "U13") (pin "9") (pinfunction "VOUT2_9") (pintype "output"))
      (node (ref "U14") (pin "5") (pinfunction "EN_5") (pintype "input"))
      (node (ref "U14") (pin "7") (pinfunction "VIN_7") (pintype "input"))
      (node (ref "U14") (pin "8") (pinfunction "VIN_8") (pintype "input"))
    )
    (net (code "53") (name "VDD_12V") (class "Default")
      (node (ref "J6") (pin "1") (pinfunction "1_1") (pintype "passive"))
      (node (ref "L6") (pin "1") (pinfunction "1_1") (pintype "passive"))
    )
    (net (code "54") (name "VDD_12V_FILTERED") (class "Default")
      (node (ref "C64") (pin "1") (pinfunction "1_1") (pintype "passive"))
      (node (ref "C65") (pin "1") (pinfunction "1_1") (pintype "passive"))
      (node (ref "L6") (pin "2") (pinfunction "2_2") (pintype "passive"))
      (node (ref "U7") (pin "2") (pinfunction "VIN_2") (pintype "input"))
      (node (ref "U7") (pin "3") (pinfunction "EN_3") (pintype "input"))
    )
    (net (code "55") (name "VIN_5V_EXT_PLUG") (class "Default")
      (node (ref "C68") (pin "1") (pinfunction "1_1") (pintype "passive"))
      (node (ref "C69") (pin "1") (pinfunction "1_1") (pintype "passive"))
      (node (ref "C70") (pin "1") (pinfunction "1_1") (pintype "passive"))
      (node (ref "C71") (pin "1") (pinfunction "1_1") (pintype "passive"))
      (node (ref "C72") (pin "1") (pinfunction "1_1") (pintype "passive"))
      (node (ref "L5") (pin "1") (pinfunction "1_1") (pintype "passive"))
      (node (ref "R58") (pin "1") (pinfunction "1_1") (pintype "passive"))
      (node (ref "R63") (pin "1") (pinfunction "1_1") (pintype "passive"))
      (node (ref "U8") (pin "1") (pinfunction "IN1_1") (pintype "power_in"))
      (node (ref "U8") (pin "2") (pinfunction "IN1_2") (pintype "power_in"))
    )
    (net (code "56") (name "VIN_5V_USB_DATA") (class "Default")
      (node (ref "C78") (pin "1") (pinfunction "1_1") (pintype "passive"))
      (node (ref "FB11") (pin "2") (pintype "passive"))
    )
    (net (code "57") (name "VIN_5V_USB_POWER") (class "Default")
      (node (ref "C79") (pin "1") (pinfunction "1_1") (pintype "passive"))
      (node (ref "R70") (pin "1") (pinfunction "1_1") (pintype "passive"))
      (node (ref "U11") (pin "1") (pinfunction "IN1_1") (pintype "power_in"))
      (node (ref "U11") (pin "2") (pinfunction "IN1_2") (pintype "power_in"))
    )
    (net (code "58") (name "VTTVREF") (class "Default")
      (node (ref "C126") (pin "1") (pinfunction "1_1") (pintype "passive"))
      (node (ref "C127") (pin "1") (pinfunction "1_1") (pintype "passive"))
      (node (ref "U15") (pin "6") (pinfunction "VTTREF_6") (pintype "output"))
    )
    (net (code "59") (name "VTT_0P75") (class "Default")
      (node (ref "C116") (pin "1") (pinfunction "1_1") (pintype "passive"))
      (node (ref "C117") (pin "1") (pinfunction "1_1") (pintype "passive"))
      (node (ref "U15") (pin "3") (pinfunction "VTT_3") (pintype "output"))
      (node (ref "U15") (pin "5") (pinfunction "VTTSNS_5") (pintype "input"))
    )
    (net (code "60") (name "unconnected-(U7-PG-Pad4)") (class "Default")
      (node (ref "U7") (pin "4") (pinfunction "PG_4") (pintype "output"))
    )
    (net (code "61") (name "unconnected-(U8-*STAT1-Pad14)") (class "Default")
      (node (ref "U8") (pin "14") (pinfunction "*STAT1_14") (pintype "output"))
    )
    (net (code "62") (name "unconnected-(U8-*STAT2-Pad11)") (class "Default")
      (node (ref "U8") (pin "11") (pinfunction "*STAT2_11") (pintype "output"))
    )
    (net (code "63") (name "unconnected-(U8-*WARN1-Pad13)") (class "Default")
      (node (ref "U8") (pin "13") (pinfunction "*WARN1_13") (pintype "output"))
    )
    (net (code "64") (name "unconnected-(U8-*WARN2-Pad12)") (class "Default")
      (node (ref "U8") (pin "12") (pinfunction "*WARN2_12") (pintype "output"))
    )
    (net (code "65") (name "unconnected-(U10-FLG-Pad3)") (class "Default")
      (node (ref "U10") (pin "3") (pinfunction "FLG_3") (pintype "passive"))
    )
    (net (code "66") (name "unconnected-(U11-*STAT1-Pad14)") (class "Default")
      (node (ref "U11") (pin "14") (pinfunction "*STAT1_14") (pintype "output"))
    )
    (net (code "67") (name "unconnected-(U11-*STAT2-Pad11)") (class "Default")
      (node (ref "U11") (pin "11") (pinfunction "*STAT2_11") (pintype "output"))
    )
    (net (code "68") (name "unconnected-(U11-*WARN1-Pad13)") (class "Default")
      (node (ref "U11") (pin "13") (pinfunction "*WARN1_13") (pintype "output"))
    )
    (net (code "69") (name "unconnected-(U11-*WARN2-Pad12)") (class "Default")
      (node (ref "U11") (pin "12") (pinfunction "*WARN2_12") (pintype "output"))
    )
    (net (code "70") (name "unconnected-(U13-SCL-Pad4)") (class "Default")
      (node (ref "U13") (pin "4") (pinfunction "SCL_4") (pintype "passive+no_connect"))
    )
    (net (code "71") (name "unconnected-(U13-SDA-Pad3)") (class "Default")
      (node (ref "U13") (pin "3") (pinfunction "SDA_3") (pintype "passive+no_connect"))
    )
    (net (code "72") (name "unconnected-(U13-SW1-Pad12)") (class "Default")
      (node (ref "U13") (pin "12") (pinfunction "SW1_12") (pintype "bidirectional+no_connect"))
    )
    (net (code "73") (name "unconnected-(U13-SW2-Pad11)") (class "Default")
      (node (ref "U13") (pin "11") (pinfunction "SW2_11") (pintype "bidirectional+no_connect"))
    )
  )
)
